# Wyswietlacz.net
KiCad netlist of a schematic drawn in Altium Designer
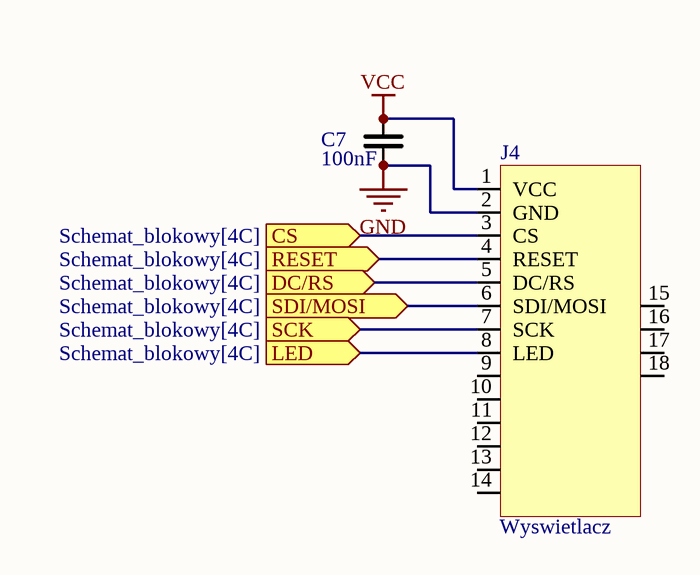
[diagram p0: Wyswietlacz.SchDoc]

(export (version "E")
  (design (tool "Eeschema 10.0.6"))
  (components
    (comp (ref "C7")
      (value "100nF")
      (footprint "0603_CAP")
      (description "Ceramic capacitor")
      (libsource (lib "Cap") (part "Cap"))
    )
    (comp (ref "J4")
      (value "Wyswietlacz")
      (footprint "pin_header_LCD")
      (description "Dispaly")
      (fields (field (name "PARTNUMBER") "ILI9486"))
      (libsource (lib "Wyswietlacz") (part "Pin Header Wyswietlacz"))
    )
  )
  (nets
    (net (code "1") (name "/CS") (class "Default")
      (node (ref "J4") (pin "3") (pinfunction "CS_3") (pintype "passive"))
    )
    (net (code "2") (name "/DC{slash}RS") (class "Default")
      (node (ref "J4") (pin "5") (pinfunction "DC/RS_5") (pintype "passive"))
    )
    (net (code "3") (name "/LED") (class "Default")
      (node (ref "J4") (pin "8") (pinfunction "LED_8") (pintype "passive"))
    )
    (net (code "4") (name "/RESET") (class "Default")
      (node (ref "J4") (pin "4") (pinfunction "RESET_4") (pintype "passive"))
    )
    (net (code "5") (name "/SCK") (class "Default")
      (node (ref "J4") (pin "7") (pinfunction "SCK_7") (pintype "passive"))
    )
    (net (code "6") (name "/SDI{slash}MOSI") (class "Default")
      (node (ref "J4") (pin "6") (pinfunction "SDI/MOSI_6") (pintype "passive"))
    )
    (net (code "7") (name "GND") (class "Default")
      (node (ref "C7") (pin "1") (pinfunction "1_1") (pintype "passive"))
      (node (ref "J4") (pin "2") (pinfunction "GND_2") (pintype "passive"))
    )
    (net (code "8") (name "VCC") (class "Default")
      (node (ref "C7") (pin "2") (pinfunction "2_2") (pintype "passive"))
      (node (ref "J4") (pin "1") (pinfunction "VCC_1") (pintype "passive"))
    )
    (net (code "9") (name "unconnected-(J4-Pad9)") (class "Default")
      (node (ref "J4") (pin "9") (pintype "passive"))
    )
    (net (code "10") (name "unconnected-(J4-Pad10)") (class "Default")
      (node (ref "J4") (pin "10") (pintype "passive"))
    )
    (net (code "11") (name "unconnected-(J4-Pad11)") (class "Default")
      (node (ref "J4") (pin "11") (pintype "passive"))
    )
    (net (code "12") (name "unconnected-(J4-Pad12)") (class "Default")
      (node (ref "J4") (pin "12") (pintype "passive"))
    )
    (net (code "13") (name "unconnected-(J4-Pad13)") (class "Default")
      (node (ref "J4") (pin "13") (pintype "passive"))
    )
    (net (code "14") (name "unconnected-(J4-Pad14)") (class "Default")
      (node (ref "J4") (pin "14") (pintype "passive"))
    )
    (net (code "15") (name "unconnected-(J4-Pad15)") (class "Default")
      (node (ref "J4") (pin "15") (pintype "passive"))
    )
    (net (code "16") (name "unconnected-(J4-Pad16)") (class "Default")
      (node (ref "J4") (pin "16") (pintype "passive"))
    )
    (net (code "17") (name "unconnected-(J4-Pad17)") (class "Default")
      (node (ref "J4") (pin "17") (pintype "passive"))
    )
    (net (code "18") (name "unconnected-(J4-Pad18)") (class "Default")
      (node (ref "J4") (pin "18") (pintype "passive"))
    )
  )
)
